# Lumazoid_v1_0.net
KiCad netlist of a schematic drawn in EAGLE
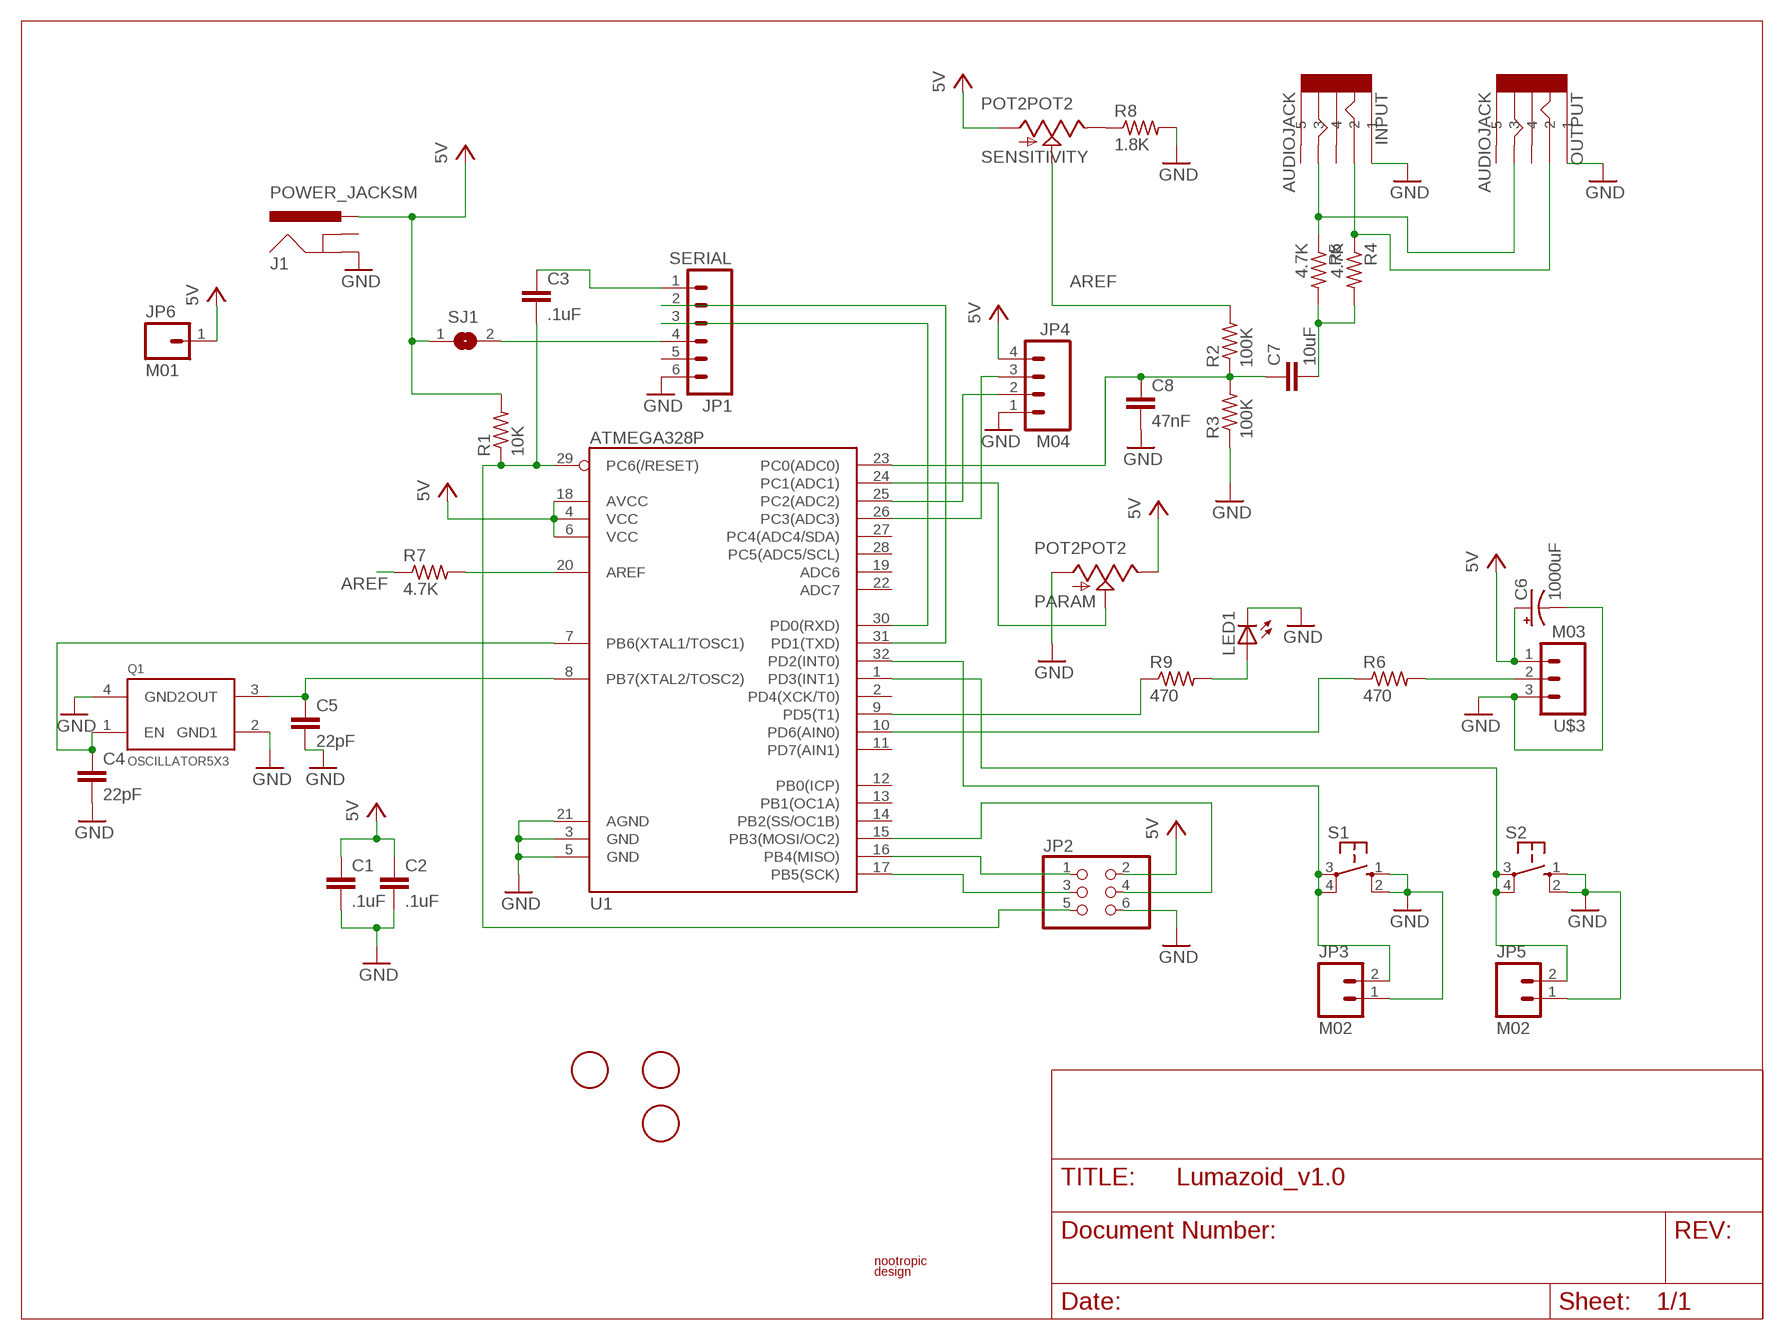
[diagram p0: schematic, sheet 1]

(export (version "E")
  (design (tool "Eeschema 10.0.6"))
  (components
    (comp (ref "C1")
      (value ".1uF")
      (footprint "eagle-import:C0603")
      (libsource (lib "eagle-import") (part "CAPC0603"))
    )
    (comp (ref "C2")
      (value ".1uF")
      (footprint "eagle-import:C0603")
      (libsource (lib "eagle-import") (part "CAPC0603"))
    )
    (comp (ref "C3")
      (value ".1uF")
      (footprint "eagle-import:C0603")
      (libsource (lib "eagle-import") (part "CAPC0603"))
    )
    (comp (ref "C4")
      (value "22pF")
      (footprint "eagle-import:C0603")
      (libsource (lib "eagle-import") (part "CAPC0603"))
    )
    (comp (ref "C5")
      (value "22pF")
      (footprint "eagle-import:C0603")
      (libsource (lib "eagle-import") (part "CAPC0603"))
    )
    (comp (ref "C6")
      (value "1000uF")
      (footprint "eagle-import:E5-10,5")
      (libsource (lib "eagle-import") (part "CPOL-USE5-10.5"))
    )
    (comp (ref "C7")
      (value "10uF")
      (footprint "eagle-import:C1206")
      (libsource (lib "eagle-import") (part "CAPC1206"))
    )
    (comp (ref "C8")
      (value "47nF")
      (footprint "eagle-import:C0603")
      (libsource (lib "eagle-import") (part "CAPC0603"))
    )
    (comp (ref "FID1")
      (value "FIDUCIAL")
      (footprint "eagle-import:FIDUCIAL_1MM")
      (libsource (lib "eagle-import") (part "FIDUCIAL"))
    )
    (comp (ref "FID2")
      (value "FIDUCIAL")
      (footprint "eagle-import:FIDUCIAL_1MM")
      (libsource (lib "eagle-import") (part "FIDUCIAL"))
    )
    (comp (ref "FID3")
      (value "FIDUCIAL")
      (footprint "eagle-import:FIDUCIAL_1MM")
      (libsource (lib "eagle-import") (part "FIDUCIAL"))
    )
    (comp (ref "INPUT")
      (value "AUDIOJACK")
      (footprint "eagle-import:AUDIOJACK")
      (libsource (lib "eagle-import") (part "AUDIOJACK"))
    )
    (comp (ref "J1")
      (value "POWER_JACKSM")
      (footprint "eagle-import:POWER_JACK_SM")
      (libsource (lib "eagle-import") (part "POWER_JACKSM"))
    )
    (comp (ref "JP1")
      (value "SERIAL")
      (footprint "eagle-import:1X06")
      (libsource (lib "eagle-import") (part "M06"))
    )
    (comp (ref "JP2")
      (value "PINHD-2X3")
      (footprint "eagle-import:2X03")
      (libsource (lib "eagle-import") (part "PINHD-2X3"))
    )
    (comp (ref "JP3")
      (value "M02")
      (footprint "eagle-import:1X02")
      (libsource (lib "eagle-import") (part "M02"))
    )
    (comp (ref "JP4")
      (value "M04")
      (footprint "eagle-import:1X04")
      (libsource (lib "eagle-import") (part "M04"))
    )
    (comp (ref "JP5")
      (value "M02")
      (footprint "eagle-import:1X02")
      (libsource (lib "eagle-import") (part "M02"))
    )
    (comp (ref "JP6")
      (value "M01")
      (footprint "eagle-import:1X01")
      (libsource (lib "eagle-import") (part "M01"))
    )
    (comp (ref "LED1")
      (value "LEDCHIPLED_0805")
      (footprint "eagle-import:CHIPLED_0805")
      (libsource (lib "eagle-import") (part "LEDCHIPLED_0805"))
    )
    (comp (ref "OUTPUT")
      (value "AUDIOJACK")
      (footprint "eagle-import:AUDIOJACK")
      (libsource (lib "eagle-import") (part "AUDIOJACK"))
    )
    (comp (ref "PARAM")
      (value "POT2POT2")
      (footprint "eagle-import:ALPS_POT")
      (libsource (lib "eagle-import") (part "POT2POT2"))
    )
    (comp (ref "Q1")
      (value "OSCILLATOR5X3")
      (footprint "eagle-import:CRYSTAL-SMD-5X3")
      (libsource (lib "eagle-import") (part "OSCILLATOR5X3"))
    )
    (comp (ref "R1")
      (value "10K")
      (footprint "eagle-import:R0603")
      (libsource (lib "eagle-import") (part "R-USR0603"))
    )
    (comp (ref "R2")
      (value "100K")
      (footprint "eagle-import:R0603")
      (libsource (lib "eagle-import") (part "R-USR0603"))
    )
    (comp (ref "R3")
      (value "100K")
      (footprint "eagle-import:R0603")
      (libsource (lib "eagle-import") (part "R-USR0603"))
    )
    (comp (ref "R4")
      (value "4.7K")
      (footprint "eagle-import:R0603")
      (libsource (lib "eagle-import") (part "R-USR0603"))
    )
    (comp (ref "R5")
      (value "4.7K")
      (footprint "eagle-import:R0603")
      (libsource (lib "eagle-import") (part "R-USR0603"))
    )
    (comp (ref "R6")
      (value "470")
      (footprint "eagle-import:R0603")
      (libsource (lib "eagle-import") (part "R-USR0603"))
    )
    (comp (ref "R7")
      (value "4.7K")
      (footprint "eagle-import:R0603")
      (libsource (lib "eagle-import") (part "R-USR0603"))
    )
    (comp (ref "R8")
      (value "1.8K")
      (footprint "eagle-import:R0603")
      (libsource (lib "eagle-import") (part "R-USR0603"))
    )
    (comp (ref "R9")
      (value "470")
      (footprint "eagle-import:R0603")
      (libsource (lib "eagle-import") (part "R-USR0603"))
    )
    (comp (ref "S1")
      (value "SWITCH-TACT6MMSMT-J")
      (footprint "eagle-import:DTSM-6-JBEND")
      (libsource (lib "eagle-import") (part "SWITCH-TACT6MMSMT-J"))
    )
    (comp (ref "S2")
      (value "SWITCH-TACT6MMSMT-J")
      (footprint "eagle-import:DTSM-6-JBEND")
      (libsource (lib "eagle-import") (part "SWITCH-TACT6MMSMT-J"))
    )
    (comp (ref "SENSITIVITY")
      (value "POT2POT2")
      (footprint "eagle-import:ALPS_POT")
      (libsource (lib "eagle-import") (part "POT2POT2"))
    )
    (comp (ref "SJ1") (value "SJ") (footprint "eagle-import:SJ") (libsource (lib "eagle-import") (part "SJ")))
    (comp (ref "U$1")
      (value "LOGO")
      (footprint "eagle-import:LOGO_SMALL")
      (libsource (lib "eagle-import") (part "LOGO"))
    )
    (comp (ref "U$3")
      (value "M03")
      (footprint "eagle-import:1X03")
      (libsource (lib "eagle-import") (part "M03"))
    )
    (comp (ref "U1")
      (value "ATMEGA328P")
      (footprint "eagle-import:TQFP32-08")
      (libsource (lib "eagle-import") (part "ATMEGA328_SMT"))
    )
  )
  (nets
    (net (code "1") (name "/AREF") (class "Default")
      (node (ref "R2") (pin "2") (pinfunction "2_2") (pintype "passive"))
      (node (ref "R7") (pin "1") (pinfunction "1_1") (pintype "passive"))
      (node (ref "SENSITIVITY") (pin "P$2") (pinfunction "2_P$2") (pintype "passive"))
    )
    (net (code "2") (name "5V") (class "Default")
      (node (ref "C1") (pin "1") (pinfunction "1_1") (pintype "passive"))
      (node (ref "C2") (pin "1") (pinfunction "1_1") (pintype "passive"))
      (node (ref "C6") (pin "+") (pinfunction "+_+") (pintype "passive"))
      (node (ref "J1") (pin "PWR") (pinfunction "PWR_PWR") (pintype "bidirectional"))
      (node (ref "JP2") (pin "2") (pinfunction "2_2") (pintype "passive"))
      (node (ref "JP4") (pin "4") (pinfunction "4_4") (pintype "passive"))
      (node (ref "JP6") (pin "1") (pinfunction "1_1") (pintype "passive"))
      (node (ref "PARAM") (pin "P$3") (pinfunction "3_P$3") (pintype "passive"))
      (node (ref "R1") (pin "2") (pinfunction "2_2") (pintype "passive"))
      (node (ref "SENSITIVITY") (pin "P$1") (pinfunction "1_P$1") (pintype "passive"))
      (node (ref "SJ1") (pin "1") (pinfunction "1_1") (pintype "passive"))
      (node (ref "U$3") (pin "1") (pinfunction "2_1") (pintype "passive"))
      (node (ref "U1") (pin "18") (pinfunction "AVCC_18") (pintype "bidirectional"))
      (node (ref "U1") (pin "4") (pinfunction "VCC_4") (pintype "bidirectional"))
      (node (ref "U1") (pin "6") (pinfunction "VCC_6") (pintype "bidirectional"))
    )
    (net (code "3") (name "GND") (class "Default")
      (node (ref "C1") (pin "2") (pinfunction "2_2") (pintype "passive"))
      (node (ref "C2") (pin "2") (pinfunction "2_2") (pintype "passive"))
      (node (ref "C4") (pin "2") (pinfunction "2_2") (pintype "passive"))
      (node (ref "C5") (pin "2") (pinfunction "2_2") (pintype "passive"))
      (node (ref "C6") (pin "-") (pinfunction "-_-") (pintype "passive"))
      (node (ref "C8") (pin "2") (pinfunction "2_2") (pintype "passive"))
      (node (ref "INPUT") (pin "1") (pinfunction "1_1") (pintype "bidirectional"))
      (node (ref "J1") (pin "GND") (pinfunction "GND_GND") (pintype "bidirectional"))
      (node (ref "JP1") (pin "6") (pinfunction "6_6") (pintype "passive"))
      (node (ref "JP2") (pin "6") (pinfunction "6_6") (pintype "passive"))
      (node (ref "JP3") (pin "1") (pinfunction "1_1") (pintype "passive"))
      (node (ref "JP4") (pin "1") (pinfunction "1_1") (pintype "passive"))
      (node (ref "JP5") (pin "1") (pinfunction "1_1") (pintype "passive"))
      (node (ref "LED1") (pin "C") (pinfunction "C_C") (pintype "passive"))
      (node (ref "OUTPUT") (pin "1") (pinfunction "1_1") (pintype "bidirectional"))
      (node (ref "PARAM") (pin "P$1") (pinfunction "1_P$1") (pintype "passive"))
      (node (ref "Q1") (pin "2") (pinfunction "GND1_2") (pintype "bidirectional"))
      (node (ref "Q1") (pin "4") (pinfunction "GND2_4") (pintype "bidirectional"))
      (node (ref "R3") (pin "1") (pinfunction "1_1") (pintype "passive"))
      (node (ref "R8") (pin "2") (pinfunction "2_2") (pintype "passive"))
      (node (ref "S1") (pin "1") (pinfunction "S_1") (pintype "passive"))
      (node (ref "S1") (pin "2") (pinfunction "S1_2") (pintype "passive"))
      (node (ref "S2") (pin "1") (pinfunction "S_1") (pintype "passive"))
      (node (ref "S2") (pin "2") (pinfunction "S1_2") (pintype "passive"))
      (node (ref "U$3") (pin "3") (pinfunction "4_3") (pintype "passive"))
      (node (ref "U1") (pin "21") (pinfunction "AGND_21") (pintype "bidirectional"))
      (node (ref "U1") (pin "3") (pinfunction "GND_3") (pintype "bidirectional"))
      (node (ref "U1") (pin "5") (pinfunction "GND_5") (pintype "bidirectional"))
    )
    (net (code "4") (name "Net-(C3-Pad1)") (class "Default")
      (node (ref "C3") (pin "1") (pinfunction "1_1") (pintype "passive"))
      (node (ref "JP1") (pin "1") (pinfunction "1_1") (pintype "passive"))
    )
    (net (code "5") (name "Net-(C7-Pad2)") (class "Default")
      (node (ref "C7") (pin "2") (pinfunction "2_2") (pintype "passive"))
      (node (ref "R4") (pin "2") (pinfunction "2_2") (pintype "passive"))
      (node (ref "R5") (pin "2") (pinfunction "2_2") (pintype "passive"))
    )
    (net (code "6") (name "Net-(INPUT-Pad2)") (class "Default")
      (node (ref "INPUT") (pin "2") (pinfunction "2_2") (pintype "bidirectional"))
      (node (ref "OUTPUT") (pin "2") (pinfunction "2_2") (pintype "bidirectional"))
      (node (ref "R4") (pin "1") (pinfunction "1_1") (pintype "passive"))
    )
    (net (code "7") (name "Net-(INPUT-Pad3)") (class "Default")
      (node (ref "INPUT") (pin "3") (pinfunction "3_3") (pintype "bidirectional"))
      (node (ref "OUTPUT") (pin "3") (pinfunction "3_3") (pintype "bidirectional"))
      (node (ref "R5") (pin "1") (pinfunction "1_1") (pintype "passive"))
    )
    (net (code "8") (name "Net-(JP1-Pad4)") (class "Default")
      (node (ref "JP1") (pin "4") (pinfunction "4_4") (pintype "passive"))
      (node (ref "SJ1") (pin "2") (pinfunction "2_2") (pintype "passive"))
    )
    (net (code "9") (name "Net-(LED1-PadA)") (class "Default")
      (node (ref "LED1") (pin "A") (pinfunction "A_A") (pintype "passive"))
      (node (ref "R9") (pin "2") (pinfunction "2_2") (pintype "passive"))
    )
    (net (code "10") (name "Net-(PARAM-2)") (class "Default")
      (node (ref "PARAM") (pin "P$2") (pinfunction "2_P$2") (pintype "passive"))
      (node (ref "U1") (pin "24") (pinfunction "PC1(ADC1)_24") (pintype "bidirectional"))
    )
    (net (code "11") (name "Net-(Q1-EN)") (class "Default")
      (node (ref "C4") (pin "1") (pinfunction "1_1") (pintype "passive"))
      (node (ref "Q1") (pin "1") (pinfunction "EN_1") (pintype "bidirectional"))
      (node (ref "U1") (pin "7") (pinfunction "PB6(XTAL1/TOSC1)_7") (pintype "bidirectional"))
    )
    (net (code "12") (name "Net-(Q1-OUT)") (class "Default")
      (node (ref "C5") (pin "1") (pinfunction "1_1") (pintype "passive"))
      (node (ref "Q1") (pin "3") (pinfunction "OUT_3") (pintype "bidirectional"))
      (node (ref "U1") (pin "8") (pinfunction "PB7(XTAL2/TOSC2)_8") (pintype "bidirectional"))
    )
    (net (code "13") (name "Net-(S1-P)") (class "Default")
      (node (ref "JP3") (pin "2") (pinfunction "2_2") (pintype "passive"))
      (node (ref "S1") (pin "3") (pinfunction "P_3") (pintype "passive"))
      (node (ref "S1") (pin "4") (pinfunction "P1_4") (pintype "passive"))
      (node (ref "U1") (pin "32") (pinfunction "PD2(INT0)_32") (pintype "bidirectional"))
    )
    (net (code "14") (name "Net-(S2-P)") (class "Default")
      (node (ref "JP5") (pin "2") (pinfunction "2_2") (pintype "passive"))
      (node (ref "S2") (pin "3") (pinfunction "P_3") (pintype "passive"))
      (node (ref "S2") (pin "4") (pinfunction "P1_4") (pintype "passive"))
      (node (ref "U1") (pin "1") (pinfunction "PD3(INT1)_1") (pintype "bidirectional"))
    )
    (net (code "15") (name "Net-(SENSITIVITY-3)") (class "Default")
      (node (ref "R8") (pin "1") (pinfunction "1_1") (pintype "passive"))
      (node (ref "SENSITIVITY") (pin "P$3") (pinfunction "3_P$3") (pintype "passive"))
    )
    (net (code "16") (name "Net-(U$3-3)") (class "Default")
      (node (ref "R6") (pin "2") (pinfunction "2_2") (pintype "passive"))
      (node (ref "U$3") (pin "2") (pinfunction "3_2") (pintype "passive"))
    )
    (net (code "17") (name "Net-(U1-AREF)") (class "Default")
      (node (ref "R7") (pin "2") (pinfunction "2_2") (pintype "passive"))
      (node (ref "U1") (pin "20") (pinfunction "AREF_20") (pintype "bidirectional"))
    )
    (net (code "18") (name "Net-(U1-PB3(MOSI{slash}OC2))") (class "Default")
      (node (ref "JP2") (pin "4") (pinfunction "4_4") (pintype "passive"))
      (node (ref "U1") (pin "15") (pinfunction "PB3(MOSI/OC2)_15") (pintype "bidirectional"))
    )
    (net (code "19") (name "Net-(U1-PB4(MISO))") (class "Default")
      (node (ref "JP2") (pin "1") (pinfunction "1_1") (pintype "passive"))
      (node (ref "U1") (pin "16") (pinfunction "PB4(MISO)_16") (pintype "bidirectional"))
    )
    (net (code "20") (name "Net-(U1-PB5(SCK))") (class "Default")
      (node (ref "JP2") (pin "3") (pinfunction "3_3") (pintype "passive"))
      (node (ref "U1") (pin "17") (pinfunction "PB5(SCK)_17") (pintype "bidirectional"))
    )
    (net (code "21") (name "Net-(U1-PC0(ADC0))") (class "Default")
      (node (ref "C7") (pin "1") (pinfunction "1_1") (pintype "passive"))
      (node (ref "C8") (pin "1") (pinfunction "1_1") (pintype "passive"))
      (node (ref "R2") (pin "1") (pinfunction "1_1") (pintype "passive"))
      (node (ref "R3") (pin "2") (pinfunction "2_2") (pintype "passive"))
      (node (ref "U1") (pin "23") (pinfunction "PC0(ADC0)_23") (pintype "bidirectional"))
    )
    (net (code "22") (name "Net-(U1-PC2(ADC2))") (class "Default")
      (node (ref "JP4") (pin "2") (pinfunction "2_2") (pintype "passive"))
      (node (ref "U1") (pin "25") (pinfunction "PC2(ADC2)_25") (pintype "bidirectional"))
    )
    (net (code "23") (name "Net-(U1-PC3(ADC3))") (class "Default")
      (node (ref "JP4") (pin "3") (pinfunction "3_3") (pintype "passive"))
      (node (ref "U1") (pin "26") (pinfunction "PC3(ADC3)_26") (pintype "bidirectional"))
    )
    (net (code "24") (name "Net-(U1-PC6({slash}RESET))") (class "Default")
      (node (ref "C3") (pin "2") (pinfunction "2_2") (pintype "passive"))
      (node (ref "JP2") (pin "5") (pinfunction "5_5") (pintype "passive"))
      (node (ref "R1") (pin "1") (pinfunction "1_1") (pintype "passive"))
      (node (ref "U1") (pin "29") (pinfunction "PC6(/RESET)_29") (pintype "bidirectional"))
    )
    (net (code "25") (name "Net-(U1-PD0(RXD))") (class "Default")
      (node (ref "JP1") (pin "3") (pinfunction "3_3") (pintype "passive"))
      (node (ref "U1") (pin "30") (pinfunction "PD0(RXD)_30") (pintype "bidirectional"))
    )
    (net (code "26") (name "Net-(U1-PD1(TXD))") (class "Default")
      (node (ref "JP1") (pin "2") (pinfunction "2_2") (pintype "passive"))
      (node (ref "U1") (pin "31") (pinfunction "PD1(TXD)_31") (pintype "bidirectional"))
    )
    (net (code "27") (name "Net-(U1-PD5(T1))") (class "Default")
      (node (ref "R9") (pin "1") (pinfunction "1_1") (pintype "passive"))
      (node (ref "U1") (pin "9") (pinfunction "PD5(T1)_9") (pintype "bidirectional"))
    )
    (net (code "28") (name "Net-(U1-PD6(AIN0))") (class "Default")
      (node (ref "R6") (pin "1") (pinfunction "1_1") (pintype "passive"))
      (node (ref "U1") (pin "10") (pinfunction "PD6(AIN0)_10") (pintype "bidirectional"))
    )
    (net (code "29") (name "unconnected-(INPUT-Pad4)") (class "Default")
      (node (ref "INPUT") (pin "4") (pinfunction "4_4") (pintype "bidirectional"))
    )
    (net (code "30") (name "unconnected-(INPUT-Pad5)") (class "Default")
      (node (ref "INPUT") (pin "5") (pinfunction "5_5") (pintype "bidirectional"))
    )
    (net (code "31") (name "unconnected-(J1-PadGNDBREAK)") (class "Default")
      (node (ref "J1") (pin "GNDBREAK") (pinfunction "GNDBREAK_GNDBREAK") (pintype "bidirectional"))
    )
    (net (code "32") (name "unconnected-(JP1-Pad5)") (class "Default")
      (node (ref "JP1") (pin "5") (pinfunction "5_5") (pintype "passive"))
    )
    (net (code "33") (name "unconnected-(OUTPUT-Pad4)") (class "Default")
      (node (ref "OUTPUT") (pin "4") (pinfunction "4_4") (pintype "bidirectional"))
    )
    (net (code "34") (name "unconnected-(OUTPUT-Pad5)") (class "Default")
      (node (ref "OUTPUT") (pin "5") (pinfunction "5_5") (pintype "bidirectional"))
    )
    (net (code "35") (name "unconnected-(U1-ADC6-Pad19)") (class "Default")
      (node (ref "U1") (pin "19") (pinfunction "ADC6_19") (pintype "bidirectional"))
    )
    (net (code "36") (name "unconnected-(U1-ADC7-Pad22)") (class "Default")
      (node (ref "U1") (pin "22") (pinfunction "ADC7_22") (pintype "bidirectional"))
    )
    (net (code "37") (name "unconnected-(U1-PB0(ICP)-Pad12)") (class "Default")
      (node (ref "U1") (pin "12") (pinfunction "PB0(ICP)_12") (pintype "bidirectional"))
    )
    (net (code "38") (name "unconnected-(U1-PB1(OC1A)-Pad13)") (class "Default")
      (node (ref "U1") (pin "13") (pinfunction "PB1(OC1A)_13") (pintype "bidirectional"))
    )
    (net (code "39") (name "unconnected-(U1-PB2(SS{slash}OC1B)-Pad14)") (class "Default")
      (node (ref "U1") (pin "14") (pinfunction "PB2(SS/OC1B)_14") (pintype "bidirectional"))
    )
    (net (code "40") (name "unconnected-(U1-PC4(ADC4{slash}SDA)-Pad27)") (class "Default")
      (node (ref "U1") (pin "27") (pinfunction "PC4(ADC4/SDA)_27") (pintype "bidirectional"))
    )
    (net (code "41") (name "unconnected-(U1-PC5(ADC5{slash}SCL)-Pad28)") (class "Default")
      (node (ref "U1") (pin "28") (pinfunction "PC5(ADC5/SCL)_28") (pintype "bidirectional"))
    )
    (net (code "42") (name "unconnected-(U1-PD4(XCK{slash}T0)-Pad2)") (class "Default")
      (node (ref "U1") (pin "2") (pinfunction "PD4(XCK/T0)_2") (pintype "bidirectional"))
    )
    (net (code "43") (name "unconnected-(U1-PD7(AIN1)-Pad11)") (class "Default")
      (node (ref "U1") (pin "11") (pinfunction "PD7(AIN1)_11") (pintype "bidirectional"))
    )
  )
)
